# Power.net
KiCad netlist of a schematic drawn in Altium Designer
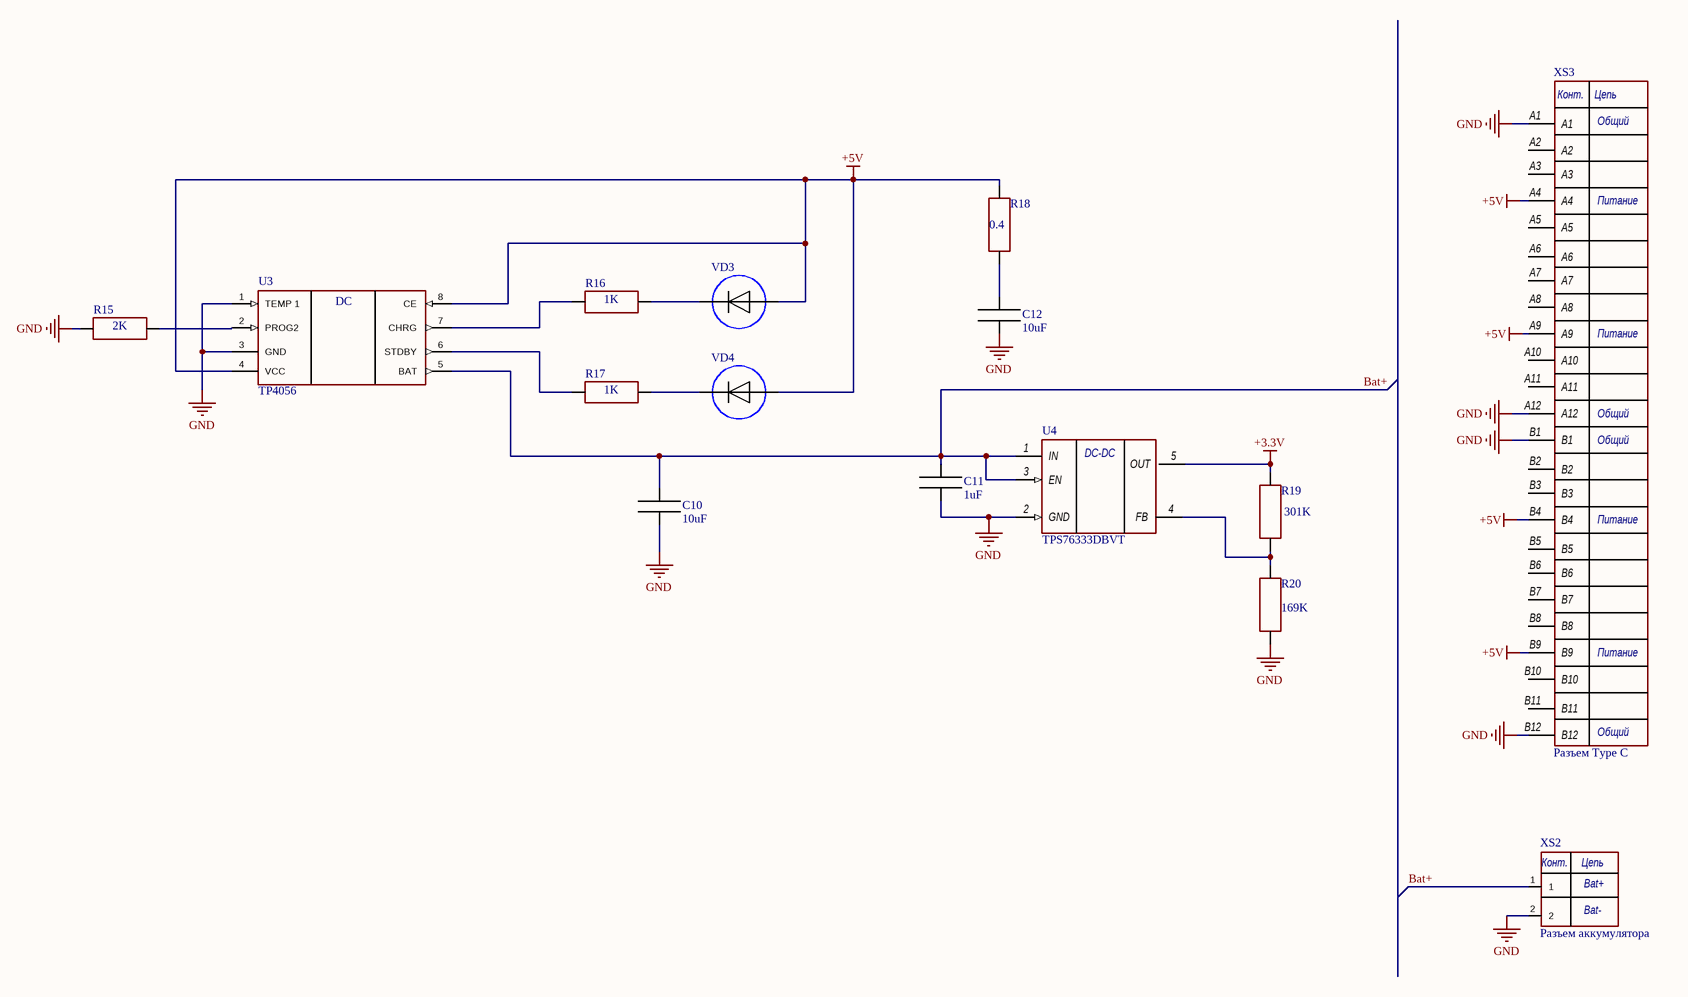
[diagram p0: Power.SchDoc]

(export (version "E")
  (design (tool "Eeschema 10.0.6"))
  (components
    (comp (ref "C10") (value "10uF") (footprint "0402") (libsource (lib "AD8233") (part "Конденсатор")))
    (comp (ref "C11") (value "1uF") (footprint "0402") (libsource (lib "AD8233") (part "Конденсатор")))
    (comp (ref "C12") (value "10uF") (footprint "0402") (libsource (lib "AD8233") (part "Конденсатор")))
    (comp (ref "R15") (value "2K") (footprint "0402") (libsource (lib "") (part "Резистор_1")))
    (comp (ref "R16") (value "1K") (footprint "0402") (libsource (lib "") (part "Резистор_1")))
    (comp (ref "R17") (value "1K") (footprint "0402") (libsource (lib "") (part "Резистор_1")))
    (comp (ref "R18") (value "0.4") (footprint "0402") (libsource (lib "AD8233") (part "Резистор")))
    (comp (ref "R19") (value "301K") (footprint "0402") (libsource (lib "AD8233") (part "Резистор")))
    (comp (ref "R20") (value "169K") (footprint "0402") (libsource (lib "AD8233") (part "Резистор")))
    (comp (ref "U3") (value "TP4056") (footprint "SOP-8") (libsource (lib "AD8233") (part "TP4056")))
    (comp (ref "U4")
      (value "TPS76333DBVT")
      (footprint "SOT23-5")
      (libsource (lib "AD8233") (part "TPS76333DBVT"))
    )
    (comp (ref "VD3") (value "Светодиод") (footprint "0402") (libsource (lib "AD8233") (part "Светодиод")))
    (comp (ref "VD4") (value "Светодиод") (footprint "0402") (libsource (lib "AD8233") (part "Светодиод")))
    (comp (ref "XS2")
      (value "Разъем аккумулятора")
      (footprint "PIN 2")
      (libsource (lib "AD8233") (part "Разъем 2"))
    )
    (comp (ref "XS3")
      (value "Разъем Type C")
      (footprint "USB Type C")
      (libsource (lib "AD8233") (part "Разъем Type C"))
    )
  )
  (nets
    (net (code "1") (name "+3.3V") (class "Default")
      (node (ref "R19") (pin "2") (pinfunction "2_2") (pintype "passive"))
      (node (ref "U4") (pin "5") (pinfunction "OUT_5") (pintype "power_in"))
    )
    (net (code "2") (name "+5V") (class "Default")
      (node (ref "R18") (pin "2") (pinfunction "2_2") (pintype "passive"))
      (node (ref "U3") (pin "4") (pinfunction "VCC_4") (pintype "power_in"))
      (node (ref "U3") (pin "8") (pinfunction "CE_8") (pintype "input"))
      (node (ref "VD3") (pin "1") (pinfunction "1_1") (pintype "passive"))
      (node (ref "VD4") (pin "1") (pinfunction "1_1") (pintype "passive"))
      (node (ref "XS3") (pin "A4") (pinfunction "A4_A4") (pintype "passive"))
      (node (ref "XS3") (pin "A9") (pinfunction "A9_A9") (pintype "passive"))
      (node (ref "XS3") (pin "B4") (pinfunction "B4_B4") (pintype "passive"))
      (node (ref "XS3") (pin "B9") (pinfunction "B9_B9") (pintype "passive"))
    )
    (net (code "3") (name "/Bat+") (class "Default")
      (node (ref "C10") (pin "2") (pinfunction "2_2") (pintype "passive"))
      (node (ref "C11") (pin "2") (pinfunction "2_2") (pintype "passive"))
      (node (ref "U3") (pin "5") (pinfunction "BAT_5") (pintype "output"))
      (node (ref "U4") (pin "1") (pinfunction "IN_1") (pintype "power_in"))
      (node (ref "U4") (pin "3") (pinfunction "EN_3") (pintype "input"))
      (node (ref "XS2") (pin "1") (pinfunction "1_1") (pintype "power_in"))
    )
    (net (code "4") (name "GND") (class "Default")
      (node (ref "C10") (pin "1") (pinfunction "1_1") (pintype "passive"))
      (node (ref "C11") (pin "1") (pinfunction "1_1") (pintype "passive"))
      (node (ref "C12") (pin "1") (pinfunction "1_1") (pintype "passive"))
      (node (ref "R15") (pin "1") (pinfunction "1_1") (pintype "passive"))
      (node (ref "R20") (pin "1") (pinfunction "1_1") (pintype "passive"))
      (node (ref "U3") (pin "1") (pinfunction "TEMP_1_1") (pintype "input"))
      (node (ref "U3") (pin "3") (pinfunction "GND_3") (pintype "power_in"))
      (node (ref "U4") (pin "2") (pinfunction "GND_2") (pintype "input"))
      (node (ref "XS2") (pin "2") (pinfunction "2_2") (pintype "power_in"))
      (node (ref "XS3") (pin "A1") (pinfunction "A1_A1") (pintype "passive"))
      (node (ref "XS3") (pin "A12") (pinfunction "A12_A12") (pintype "passive"))
      (node (ref "XS3") (pin "B1") (pinfunction "B1_B1") (pintype "passive"))
      (node (ref "XS3") (pin "B12") (pinfunction "B12_B12") (pintype "passive"))
    )
    (net (code "5") (name "Net-(C12-Pad2)") (class "Default")
      (node (ref "C12") (pin "2") (pinfunction "2_2") (pintype "passive"))
      (node (ref "R18") (pin "1") (pinfunction "1_1") (pintype "passive"))
    )
    (net (code "6") (name "Net-(R16-Pad2)") (class "Default")
      (node (ref "R16") (pin "2") (pinfunction "2_2") (pintype "passive"))
      (node (ref "VD3") (pin "2") (pinfunction "2_2") (pintype "passive"))
    )
    (net (code "7") (name "Net-(R17-Pad2)") (class "Default")
      (node (ref "R17") (pin "2") (pinfunction "2_2") (pintype "passive"))
      (node (ref "VD4") (pin "2") (pinfunction "2_2") (pintype "passive"))
    )
    (net (code "8") (name "Net-(U3-CHRG)") (class "Default")
      (node (ref "R16") (pin "1") (pinfunction "1_1") (pintype "passive"))
      (node (ref "U3") (pin "7") (pinfunction "CHRG_7") (pintype "output"))
    )
    (net (code "9") (name "Net-(U3-PROG2)") (class "Default")
      (node (ref "R15") (pin "2") (pinfunction "2_2") (pintype "passive"))
      (node (ref "U3") (pin "2") (pinfunction "PROG2_2") (pintype "input"))
    )
    (net (code "10") (name "Net-(U3-STDBY)") (class "Default")
      (node (ref "R17") (pin "1") (pinfunction "1_1") (pintype "passive"))
      (node (ref "U3") (pin "6") (pinfunction "STDBY_6") (pintype "output"))
    )
    (net (code "11") (name "Net-(U4-FB)") (class "Default")
      (node (ref "R19") (pin "1") (pinfunction "1_1") (pintype "passive"))
      (node (ref "R20") (pin "2") (pinfunction "2_2") (pintype "passive"))
      (node (ref "U4") (pin "4") (pinfunction "FB_4") (pintype "power_in"))
    )
    (net (code "12") (name "unconnected-(XS3-PadA2)") (class "Default")
      (node (ref "XS3") (pin "A2") (pinfunction "A2_A2") (pintype "passive"))
    )
    (net (code "13") (name "unconnected-(XS3-PadA3)") (class "Default")
      (node (ref "XS3") (pin "A3") (pinfunction "A3_A3") (pintype "passive"))
    )
    (net (code "14") (name "unconnected-(XS3-PadA5)") (class "Default")
      (node (ref "XS3") (pin "A5") (pinfunction "A5_A5") (pintype "passive"))
    )
    (net (code "15") (name "unconnected-(XS3-PadA6)") (class "Default")
      (node (ref "XS3") (pin "A6") (pinfunction "A6_A6") (pintype "passive"))
    )
    (net (code "16") (name "unconnected-(XS3-PadA7)") (class "Default")
      (node (ref "XS3") (pin "A7") (pinfunction "A7_A7") (pintype "passive"))
    )
    (net (code "17") (name "unconnected-(XS3-PadA8)") (class "Default")
      (node (ref "XS3") (pin "A8") (pinfunction "A8_A8") (pintype "passive"))
    )
    (net (code "18") (name "unconnected-(XS3-PadA10)") (class "Default")
      (node (ref "XS3") (pin "A10") (pinfunction "A10_A10") (pintype "passive"))
    )
    (net (code "19") (name "unconnected-(XS3-PadA11)") (class "Default")
      (node (ref "XS3") (pin "A11") (pinfunction "A11_A11") (pintype "passive"))
    )
    (net (code "20") (name "unconnected-(XS3-PadB2)") (class "Default")
      (node (ref "XS3") (pin "B2") (pinfunction "B2_B2") (pintype "passive"))
    )
    (net (code "21") (name "unconnected-(XS3-PadB3)") (class "Default")
      (node (ref "XS3") (pin "B3") (pinfunction "B3_B3") (pintype "passive"))
    )
    (net (code "22") (name "unconnected-(XS3-PadB5)") (class "Default")
      (node (ref "XS3") (pin "B5") (pinfunction "B5_B5") (pintype "passive"))
    )
    (net (code "23") (name "unconnected-(XS3-PadB6)") (class "Default")
      (node (ref "XS3") (pin "B6") (pinfunction "B6_B6") (pintype "passive"))
    )
    (net (code "24") (name "unconnected-(XS3-PadB7)") (class "Default")
      (node (ref "XS3") (pin "B7") (pinfunction "B7_B7") (pintype "passive"))
    )
    (net (code "25") (name "unconnected-(XS3-PadB8)") (class "Default")
      (node (ref "XS3") (pin "B8") (pinfunction "B8_B8") (pintype "passive"))
    )
    (net (code "26") (name "unconnected-(XS3-PadB10)") (class "Default")
      (node (ref "XS3") (pin "B10") (pinfunction "B10_B10") (pintype "passive"))
    )
    (net (code "27") (name "unconnected-(XS3-PadB11)") (class "Default")
      (node (ref "XS3") (pin "B11") (pinfunction "B11_B11") (pintype "passive"))
    )
  )
)
